# aria_g25.net
KiCad netlist of a schematic drawn in Altium Designer
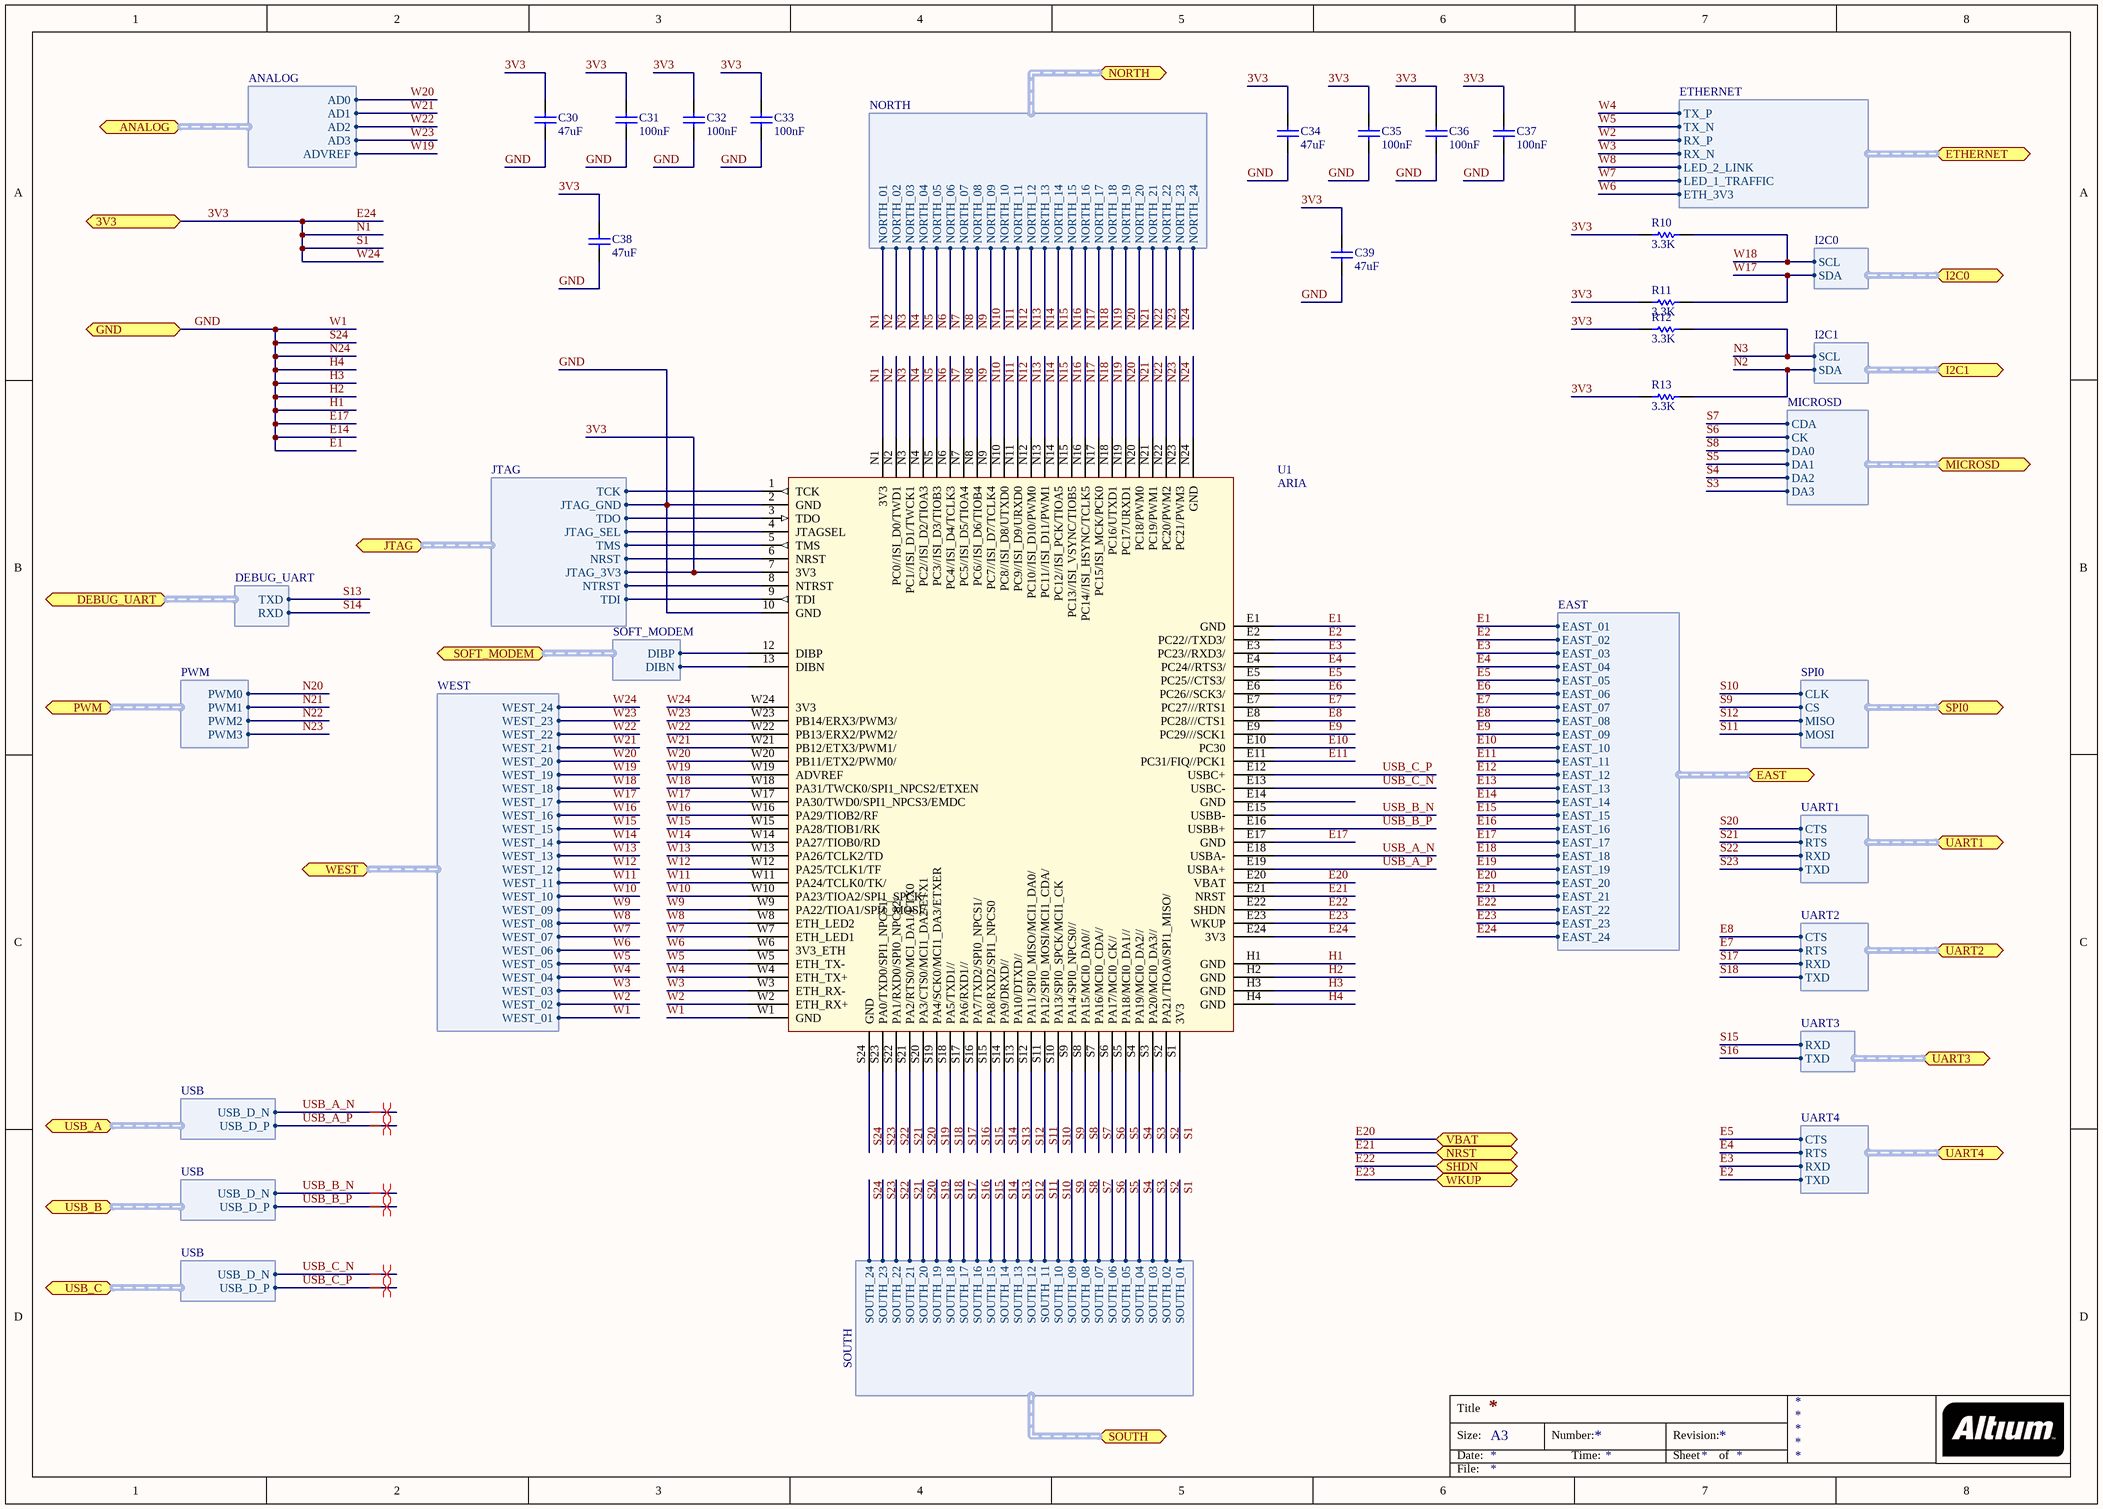
[diagram p0: aria_g25.SchDoc]

(export (version "E")
  (design (tool "Eeschema 10.0.6"))
  (components
    (comp (ref "C30")
      (value "47uF")
      (footprint "0805")
      (fields (field (name "TOLERANCE") "5%") (field (name "VOLTAGE") "10V") (field (name "Comment") "CAP"))
      (libsource (lib "gasctrl") (part "CAP"))
    )
    (comp (ref "C31")
      (value "100nF")
      (footprint "0805")
      (fields (field (name "TOLERANCE") "5%") (field (name "VOLTAGE") "10V") (field (name "Comment") "CAP"))
      (libsource (lib "gasctrl") (part "CAP"))
    )
    (comp (ref "C32")
      (value "100nF")
      (footprint "0805")
      (fields (field (name "TOLERANCE") "5%") (field (name "VOLTAGE") "10V") (field (name "Comment") "CAP"))
      (libsource (lib "gasctrl") (part "CAP"))
    )
    (comp (ref "C33")
      (value "100nF")
      (footprint "0805")
      (fields (field (name "TOLERANCE") "5%") (field (name "VOLTAGE") "10V") (field (name "Comment") "CAP"))
      (libsource (lib "gasctrl") (part "CAP"))
    )
    (comp (ref "C34")
      (value "47uF")
      (footprint "0805")
      (fields (field (name "TOLERANCE") "5%") (field (name "VOLTAGE") "10V") (field (name "Comment") "CAP"))
      (libsource (lib "gasctrl") (part "CAP"))
    )
    (comp (ref "C35")
      (value "100nF")
      (footprint "0805")
      (fields (field (name "TOLERANCE") "5%") (field (name "VOLTAGE") "10V") (field (name "Comment") "CAP"))
      (libsource (lib "gasctrl") (part "CAP"))
    )
    (comp (ref "C36")
      (value "100nF")
      (footprint "0805")
      (fields (field (name "TOLERANCE") "5%") (field (name "VOLTAGE") "10V") (field (name "Comment") "CAP"))
      (libsource (lib "gasctrl") (part "CAP"))
    )
    (comp (ref "C37")
      (value "100nF")
      (footprint "0805")
      (fields (field (name "TOLERANCE") "5%") (field (name "VOLTAGE") "10V") (field (name "Comment") "CAP"))
      (libsource (lib "gasctrl") (part "CAP"))
    )
    (comp (ref "C38")
      (value "47uF")
      (footprint "0805")
      (fields (field (name "TOLERANCE") "5%") (field (name "VOLTAGE") "10V") (field (name "Comment") "CAP"))
      (libsource (lib "gasctrl") (part "CAP"))
    )
    (comp (ref "C39")
      (value "47uF")
      (footprint "0805")
      (fields (field (name "TOLERANCE") "5%") (field (name "VOLTAGE") "10V") (field (name "Comment") "CAP"))
      (libsource (lib "gasctrl") (part "CAP"))
    )
    (comp (ref "R10")
      (value "3.3K")
      (footprint "0805")
      (fields (field (name "Comment") "RES"))
      (libsource (lib "gasctrl") (part "RES"))
    )
    (comp (ref "R11")
      (value "3.3K")
      (footprint "0805")
      (fields (field (name "Comment") "RES"))
      (libsource (lib "gasctrl") (part "RES"))
    )
    (comp (ref "R12")
      (value "3.3K")
      (footprint "0805")
      (fields (field (name "Comment") "RES"))
      (libsource (lib "gasctrl") (part "RES"))
    )
    (comp (ref "R13")
      (value "3.3K")
      (footprint "0805")
      (fields (field (name "Comment") "RES"))
      (libsource (lib "gasctrl") (part "RES"))
    )
    (comp (ref "U1")
      (value "ARIA")
      (footprint "AB ARIA 1")
      (fields (field (name "MANUFACTURER") "Acme Systems"))
      (libsource (lib "Schematics") (part "ARIA"))
    )
  )
  (nets
    (net (code "20") (name "/3V3") (class "Default")
      (node (ref "C30") (pin "2") (pinfunction "2_2") (pintype "passive"))
      (node (ref "C31") (pin "2") (pinfunction "2_2") (pintype "passive"))
      (node (ref "C32") (pin "2") (pinfunction "2_2") (pintype "passive"))
      (node (ref "C33") (pin "2") (pinfunction "2_2") (pintype "passive"))
      (node (ref "C34") (pin "2") (pinfunction "2_2") (pintype "passive"))
      (node (ref "C35") (pin "2") (pinfunction "2_2") (pintype "passive"))
      (node (ref "C36") (pin "2") (pinfunction "2_2") (pintype "passive"))
      (node (ref "C37") (pin "2") (pinfunction "2_2") (pintype "passive"))
      (node (ref "C38") (pin "2") (pinfunction "2_2") (pintype "passive"))
      (node (ref "C39") (pin "2") (pinfunction "2_2") (pintype "passive"))
      (node (ref "R10") (pin "2") (pinfunction "2_2") (pintype "passive"))
      (node (ref "R11") (pin "2") (pinfunction "2_2") (pintype "passive"))
      (node (ref "R12") (pin "2") (pinfunction "2_2") (pintype "passive"))
      (node (ref "R13") (pin "2") (pinfunction "2_2") (pintype "passive"))
      (node (ref "U1") (pin "7") (pinfunction "3V3_7") (pintype "power_in"))
      (node (ref "U1") (pin "E24") (pinfunction "3V3_E24") (pintype "passive"))
      (node (ref "U1") (pin "N1") (pinfunction "3V3_N1") (pintype "passive"))
      (node (ref "U1") (pin "S1") (pinfunction "3V3_S1") (pintype "passive"))
      (node (ref "U1") (pin "W24") (pinfunction "3V3_W24") (pintype "passive"))
    )
    (net (code "21") (name "/DIBN") (class "Default")
      (node (ref "U1") (pin "13") (pinfunction "DIBN_13") (pintype "passive"))
    )
    (net (code "22") (name "/DIBP") (class "Default")
      (node (ref "U1") (pin "12") (pinfunction "DIBP_12") (pintype "passive"))
    )
    (net (code "23") (name "/E1") (class "Default")
      (node (ref "C30") (pin "1") (pinfunction "1_1") (pintype "passive"))
      (node (ref "C31") (pin "1") (pinfunction "1_1") (pintype "passive"))
      (node (ref "C32") (pin "1") (pinfunction "1_1") (pintype "passive"))
      (node (ref "C33") (pin "1") (pinfunction "1_1") (pintype "passive"))
      (node (ref "C34") (pin "1") (pinfunction "1_1") (pintype "passive"))
      (node (ref "C35") (pin "1") (pinfunction "1_1") (pintype "passive"))
      (node (ref "C36") (pin "1") (pinfunction "1_1") (pintype "passive"))
      (node (ref "C37") (pin "1") (pinfunction "1_1") (pintype "passive"))
      (node (ref "C38") (pin "1") (pinfunction "1_1") (pintype "passive"))
      (node (ref "C39") (pin "1") (pinfunction "1_1") (pintype "passive"))
      (node (ref "U1") (pin "10") (pinfunction "GND_10") (pintype "passive"))
      (node (ref "U1") (pin "2") (pinfunction "GND_2") (pintype "power_in"))
      (node (ref "U1") (pin "E1") (pinfunction "GND_E1") (pintype "passive"))
      (node (ref "U1") (pin "E17") (pinfunction "GND_E17") (pintype "passive"))
      (node (ref "U1") (pin "H1") (pinfunction "GND_H1") (pintype "passive"))
      (node (ref "U1") (pin "H2") (pinfunction "GND_H2") (pintype "passive"))
      (node (ref "U1") (pin "H3") (pinfunction "GND_H3") (pintype "passive"))
      (node (ref "U1") (pin "H4") (pinfunction "GND_H4") (pintype "passive"))
      (node (ref "U1") (pin "N24") (pinfunction "GND_N24") (pintype "passive"))
      (node (ref "U1") (pin "S24") (pinfunction "GND_S24") (pintype "passive"))
      (node (ref "U1") (pin "W1") (pinfunction "GND_W1") (pintype "power_in"))
    )
    (net (code "24") (name "/E2") (class "Default")
      (node (ref "U1") (pin "E2") (pinfunction "PC22//TXD3/_E2") (pintype "passive"))
    )
    (net (code "25") (name "/E3") (class "Default")
      (node (ref "U1") (pin "E3") (pinfunction "PC23//RXD3/_E3") (pintype "passive"))
    )
    (net (code "26") (name "/E4") (class "Default")
      (node (ref "U1") (pin "E4") (pinfunction "PC24//RTS3/_E4") (pintype "passive"))
    )
    (net (code "27") (name "/E5") (class "Default")
      (node (ref "U1") (pin "E5") (pinfunction "PC25//CTS3/_E5") (pintype "passive"))
    )
    (net (code "28") (name "/E6") (class "Default")
      (node (ref "U1") (pin "E6") (pinfunction "PC26//SCK3/_E6") (pintype "passive"))
    )
    (net (code "29") (name "/E7") (class "Default")
      (node (ref "U1") (pin "E7") (pinfunction "PC27///RTS1_E7") (pintype "passive"))
    )
    (net (code "30") (name "/E8") (class "Default")
      (node (ref "U1") (pin "E8") (pinfunction "PC28///CTS1_E8") (pintype "passive"))
    )
    (net (code "31") (name "/E9") (class "Default")
      (node (ref "U1") (pin "E9") (pinfunction "PC29///SCK1_E9") (pintype "passive"))
    )
    (net (code "32") (name "/E10") (class "Default")
      (node (ref "U1") (pin "E10") (pinfunction "PC30_E10") (pintype "passive"))
    )
    (net (code "33") (name "/E11") (class "Default")
      (node (ref "U1") (pin "E11") (pinfunction "PC31/FIQ//PCK1_E11") (pintype "passive"))
    )
    (net (code "40") (name "/E20") (class "Default")
      (node (ref "U1") (pin "E20") (pinfunction "VBAT_E20") (pintype "passive"))
    )
    (net (code "41") (name "/E21") (class "Default")
      (node (ref "U1") (pin "E21") (pinfunction "NRST_E21") (pintype "passive"))
    )
    (net (code "42") (name "/E22") (class "Default")
      (node (ref "U1") (pin "E22") (pinfunction "SHDN_E22") (pintype "passive"))
    )
    (net (code "43") (name "/E23") (class "Default")
      (node (ref "U1") (pin "E23") (pinfunction "WKUP_E23") (pintype "passive"))
    )
    (net (code "44") (name "/JTAG_SEL") (class "Default")
      (node (ref "U1") (pin "4") (pinfunction "JTAGSEL_4") (pintype "passive"))
    )
    (net (code "45") (name "/N2") (class "Default")
      (node (ref "R13") (pin "1") (pinfunction "1_1") (pintype "passive"))
      (node (ref "U1") (pin "N2") (pinfunction "PC0//ISI_D0/TWD1_N2") (pintype "passive"))
    )
    (net (code "46") (name "/N3") (class "Default")
      (node (ref "R12") (pin "1") (pinfunction "1_1") (pintype "passive"))
      (node (ref "U1") (pin "N3") (pinfunction "PC1//ISI_D1/TWCK1_N3") (pintype "passive"))
    )
    (net (code "47") (name "/N4") (class "Default")
      (node (ref "U1") (pin "N4") (pinfunction "PC2//ISI_D2/TIOA3_N4") (pintype "passive"))
    )
    (net (code "48") (name "/N5") (class "Default")
      (node (ref "U1") (pin "N5") (pinfunction "PC3//ISI_D3/TIOB3_N5") (pintype "passive"))
    )
    (net (code "49") (name "/N6") (class "Default")
      (node (ref "U1") (pin "N6") (pinfunction "PC4//ISI_D4/TCLK3_N6") (pintype "passive"))
    )
    (net (code "50") (name "/N7") (class "Default")
      (node (ref "U1") (pin "N7") (pinfunction "PC5//ISI_D5/TIOA4_N7") (pintype "passive"))
    )
    (net (code "51") (name "/N8") (class "Default")
      (node (ref "U1") (pin "N8") (pinfunction "PC6//ISI_D6/TIOB4_N8") (pintype "passive"))
    )
    (net (code "52") (name "/N9") (class "Default")
      (node (ref "U1") (pin "N9") (pinfunction "PC7//ISI_D7/TCLK4_N9") (pintype "passive"))
    )
    (net (code "53") (name "/N10") (class "Default")
      (node (ref "U1") (pin "N10") (pinfunction "PC8//ISI_D8/UTXD0_N10") (pintype "passive"))
    )
    (net (code "54") (name "/N11") (class "Default")
      (node (ref "U1") (pin "N11") (pinfunction "PC9//ISI_D9/URXD0_N11") (pintype "passive"))
    )
    (net (code "55") (name "/N12") (class "Default")
      (node (ref "U1") (pin "N12") (pinfunction "PC10//ISI_D10/PWM0_N12") (pintype "passive"))
    )
    (net (code "56") (name "/N13") (class "Default")
      (node (ref "U1") (pin "N13") (pinfunction "PC11//ISI_D11/PWM1_N13") (pintype "passive"))
    )
    (net (code "57") (name "/N14") (class "Default")
      (node (ref "U1") (pin "N14") (pinfunction "PC12//ISI_PCK/TIOA5_N14") (pintype "passive"))
    )
    (net (code "58") (name "/N15") (class "Default")
      (node (ref "U1") (pin "N15") (pinfunction "PC13//ISI_VSYNC/TIOB5_N15") (pintype "passive"))
    )
    (net (code "59") (name "/N16") (class "Default")
      (node (ref "U1") (pin "N16") (pinfunction "PC14//ISI_HSYNC/TCLK5_N16") (pintype "passive"))
    )
    (net (code "60") (name "/N17") (class "Default")
      (node (ref "U1") (pin "N17") (pinfunction "PC15/ISI_MCK/PCK0_N17") (pintype "passive"))
    )
    (net (code "61") (name "/N18") (class "Default")
      (node (ref "U1") (pin "N18") (pinfunction "PC16/UTXD1_N18") (pintype "passive"))
    )
    (net (code "62") (name "/N19") (class "Default")
      (node (ref "U1") (pin "N19") (pinfunction "PC17/URXD1_N19") (pintype "passive"))
    )
    (net (code "63") (name "/N20") (class "Default")
      (node (ref "U1") (pin "N20") (pinfunction "PC18/PWM0_N20") (pintype "passive"))
    )
    (net (code "64") (name "/N21") (class "Default")
      (node (ref "U1") (pin "N21") (pinfunction "PC19/PWM1_N21") (pintype "passive"))
    )
    (net (code "65") (name "/N22") (class "Default")
      (node (ref "U1") (pin "N22") (pinfunction "PC20/PWM2_N22") (pintype "passive"))
    )
    (net (code "66") (name "/N23") (class "Default")
      (node (ref "U1") (pin "N23") (pinfunction "PC21/PWM3_N23") (pintype "passive"))
    )
    (net (code "67") (name "/NTRST") (class "Default")
      (node (ref "U1") (pin "8") (pinfunction "NTRST_8") (pintype "passive"))
    )
    (net (code "68") (name "/S2") (class "Default")
      (node (ref "U1") (pin "S2") (pinfunction "PA21/TIOA0/SPI1_MISO/_S2") (pintype "passive"))
    )
    (net (code "69") (name "/S3") (class "Default")
      (node (ref "U1") (pin "S3") (pinfunction "PA20/MCI0_DA3//_S3") (pintype "passive"))
    )
    (net (code "70") (name "/S4") (class "Default")
      (node (ref "U1") (pin "S4") (pinfunction "PA19/MCI0_DA2//_S4") (pintype "passive"))
    )
    (net (code "71") (name "/S5") (class "Default")
      (node (ref "U1") (pin "S5") (pinfunction "PA18/MCI0_DA1//_S5") (pintype "passive"))
    )
    (net (code "72") (name "/S6") (class "Default")
      (node (ref "U1") (pin "S6") (pinfunction "PA17/MCI0_CK//_S6") (pintype "passive"))
    )
    (net (code "73") (name "/S7") (class "Default")
      (node (ref "U1") (pin "S7") (pinfunction "PA16/MCI0_CDA//_S7") (pintype "passive"))
    )
    (net (code "74") (name "/S8") (class "Default")
      (node (ref "U1") (pin "S8") (pinfunction "PA15/MCI0_DA0//_S8") (pintype "passive"))
    )
    (net (code "75") (name "/S9") (class "Default")
      (node (ref "U1") (pin "S9") (pinfunction "PA14/SPI0_NPCS0//_S9") (pintype "passive"))
    )
    (net (code "76") (name "/S10") (class "Default")
      (node (ref "U1") (pin "S10") (pinfunction "PA13/SPI0_SPCK/MCI1_CK_S10") (pintype "passive"))
    )
    (net (code "77") (name "/S11") (class "Default")
      (node (ref "U1") (pin "S11") (pinfunction "PA12/SPI0_MOSI/MCI1_CDA/_S11") (pintype "passive"))
    )
    (net (code "78") (name "/S12") (class "Default")
      (node (ref "U1") (pin "S12") (pinfunction "PA11/SPI0_MISO/MCI1_DA0/_S12") (pintype "passive"))
    )
    (net (code "79") (name "/S13") (class "Default")
      (node (ref "U1") (pin "S13") (pinfunction "PA10/DTXD//_S13") (pintype "passive"))
    )
    (net (code "80") (name "/S14") (class "Default")
      (node (ref "U1") (pin "S14") (pinfunction "PA9/DRXD//_S14") (pintype "passive"))
    )
    (net (code "81") (name "/S15") (class "Default")
      (node (ref "U1") (pin "S15") (pinfunction "PA8/RXD2/SPI1_NPCS0_S15") (pintype "passive"))
    )
    (net (code "82") (name "/S16") (class "Default")
      (node (ref "U1") (pin "S16") (pinfunction "PA7/TXD2/SPI0_NPCS1/_S16") (pintype "passive"))
    )
    (net (code "83") (name "/S17") (class "Default")
      (node (ref "U1") (pin "S17") (pinfunction "PA6/RXD1//_S17") (pintype "passive"))
    )
    (net (code "84") (name "/S18") (class "Default")
      (node (ref "U1") (pin "S18") (pinfunction "PA5/TXD1//_S18") (pintype "passive"))
    )
    (net (code "85") (name "/S19") (class "Default")
      (node (ref "U1") (pin "S19") (pinfunction "PA4/SCK0/MCI1_DA3/ETXER_S19") (pintype "passive"))
    )
    (net (code "86") (name "/S20") (class "Default")
      (node (ref "U1") (pin "S20") (pinfunction "PA3/CTS0/MCI1_DA2/ETX1_S20") (pintype "passive"))
    )
    (net (code "87") (name "/S21") (class "Default")
      (node (ref "U1") (pin "S21") (pinfunction "PA2/RTS0/MCI_DA1/ETX0_S21") (pintype "passive"))
    )
    (net (code "88") (name "/S22") (class "Default")
      (node (ref "U1") (pin "S22") (pinfunction "PA1/RXD0/SPI0_NPCS2/_S22") (pintype "passive"))
    )
    (net (code "89") (name "/S23") (class "Default")
      (node (ref "U1") (pin "S23") (pinfunction "PA0/TXD0/SPI1_NPCS1/_S23") (pintype "passive"))
    )
    (net (code "90") (name "/TCK") (class "Default")
      (node (ref "U1") (pin "1") (pinfunction "TCK_1") (pintype "output"))
    )
    (net (code "91") (name "/TDI") (class "Default")
      (node (ref "U1") (pin "9") (pinfunction "TDI_9") (pintype "output"))
    )
    (net (code "92") (name "/TDO") (class "Default")
      (node (ref "U1") (pin "3") (pinfunction "TDO_3") (pintype "input"))
    )
    (net (code "93") (name "/TMS") (class "Default")
      (node (ref "U1") (pin "5") (pinfunction "TMS_5") (pintype "output"))
    )
    (net (code "94") (name "/USB_A_N") (class "Default")
      (node (ref "U1") (pin "E18") (pinfunction "USBA-_E18") (pintype "passive"))
    )
    (net (code "95") (name "/USB_A_P") (class "Default")
      (node (ref "U1") (pin "E19") (pinfunction "USBA+_E19") (pintype "passive"))
    )
    (net (code "96") (name "/USB_B_N") (class "Default")
      (node (ref "U1") (pin "E15") (pinfunction "USBB-_E15") (pintype "passive"))
    )
    (net (code "97") (name "/USB_B_P") (class "Default")
      (node (ref "U1") (pin "E16") (pinfunction "USBB+_E16") (pintype "passive"))
    )
    (net (code "98") (name "/USB_C_N") (class "Default")
      (node (ref "U1") (pin "E13") (pinfunction "USBC-_E13") (pintype "passive"))
    )
    (net (code "99") (name "/USB_C_P") (class "Default")
      (node (ref "U1") (pin "E12") (pinfunction "USBC+_E12") (pintype "passive"))
    )
    (net (code "100") (name "/W2") (class "Default")
      (node (ref "U1") (pin "W2") (pinfunction "ETH_RX+_W2") (pintype "passive"))
    )
    (net (code "101") (name "/W3") (class "Default")
      (node (ref "U1") (pin "W3") (pinfunction "ETH_RX-_W3") (pintype "passive"))
    )
    (net (code "102") (name "/W4") (class "Default")
      (node (ref "U1") (pin "W4") (pinfunction "ETH_TX+_W4") (pintype "passive"))
    )
    (net (code "103") (name "/W5") (class "Default")
      (node (ref "U1") (pin "W5") (pinfunction "ETH_TX-_W5") (pintype "passive"))
    )
    (net (code "104") (name "/W6") (class "Default")
      (node (ref "U1") (pin "W6") (pinfunction "3V3_ETH_W6") (pintype "passive"))
    )
    (net (code "105") (name "/W7") (class "Default")
      (node (ref "U1") (pin "W7") (pinfunction "ETH_LED1_W7") (pintype "passive"))
    )
    (net (code "106") (name "/W8") (class "Default")
      (node (ref "U1") (pin "W8") (pinfunction "ETH_LED2_W8") (pintype "passive"))
    )
    (net (code "107") (name "/W9") (class "Default")
      (node (ref "U1") (pin "W9") (pinfunction "PA22/TIOA1/SPI1_MOSI/_W9") (pintype "passive"))
    )
    (net (code "108") (name "/W10") (class "Default")
      (node (ref "U1") (pin "W10") (pinfunction "PA23/TIOA2/SPI1_SPCK/_W10") (pintype "passive"))
    )
    (net (code "109") (name "/W11") (class "Default")
      (node (ref "U1") (pin "W11") (pinfunction "PA24/TCLK0/TK/_W11") (pintype "passive"))
    )
    (net (code "110") (name "/W12") (class "Default")
      (node (ref "U1") (pin "W12") (pinfunction "PA25/TCLK1/TF_W12") (pintype "passive"))
    )
    (net (code "111") (name "/W13") (class "Default")
      (node (ref "U1") (pin "W13") (pinfunction "PA26/TCLK2/TD_W13") (pintype "passive"))
    )
    (net (code "112") (name "/W14") (class "Default")
      (node (ref "U1") (pin "W14") (pinfunction "PA27/TIOB0/RD_W14") (pintype "passive"))
    )
    (net (code "113") (name "/W15") (class "Default")
      (node (ref "U1") (pin "W15") (pinfunction "PA28/TIOB1/RK_W15") (pintype "passive"))
    )
    (net (code "114") (name "/W16") (class "Default")
      (node (ref "U1") (pin "W16") (pinfunction "PA29/TIOB2/RF_W16") (pintype "passive"))
    )
    (net (code "115") (name "/W17") (class "Default")
      (node (ref "R11") (pin "1") (pinfunction "1_1") (pintype "passive"))
      (node (ref "U1") (pin "W17") (pinfunction "PA30/TWD0/SPI1_NPCS3/EMDC_W17") (pintype "passive"))
    )
    (net (code "116") (name "/W18") (class "Default")
      (node (ref "R10") (pin "1") (pinfunction "1_1") (pintype "passive"))
      (node (ref "U1") (pin "W18") (pinfunction "PA31/TWCK0/SPI1_NPCS2/ETXEN_W18") (pintype "passive"))
    )
    (net (code "117") (name "/W19") (class "Default")
      (node (ref "U1") (pin "W19") (pinfunction "ADVREF_W19") (pintype "passive"))
    )
    (net (code "118") (name "/W20") (class "Default")
      (node (ref "U1") (pin "W20") (pinfunction "PB11/ETX2/PWM0/_W20") (pintype "passive"))
    )
    (net (code "119") (name "/W21") (class "Default")
      (node (ref "U1") (pin "W21") (pinfunction "PB12/ETX3/PWM1/_W21") (pintype "passive"))
    )
    (net (code "120") (name "/W22") (class "Default")
      (node (ref "U1") (pin "W22") (pinfunction "PB13/ERX2/PWM2/_W22") (pintype "passive"))
    )
    (net (code "121") (name "/W23") (class "Default")
      (node (ref "U1") (pin "W23") (pinfunction "PB14/ERX3/PWM3/_W23") (pintype "passive"))
    )
    (net (code "141") (name "unconnected-(U1-GND-PadE14)") (class "Default")
      (node (ref "U1") (pin "E14") (pinfunction "GND_E14") (pintype "passive"))
    )
    (net (code "142") (name "unconnected-(U1-NRST-Pad6)") (class "Default")
      (node (ref "U1") (pin "6") (pinfunction "NRST_6") (pintype "passive"))
    )
  )
)
